# Putri_Shaqila_GT1.net
KiCad netlist of a schematic drawn in EAGLE
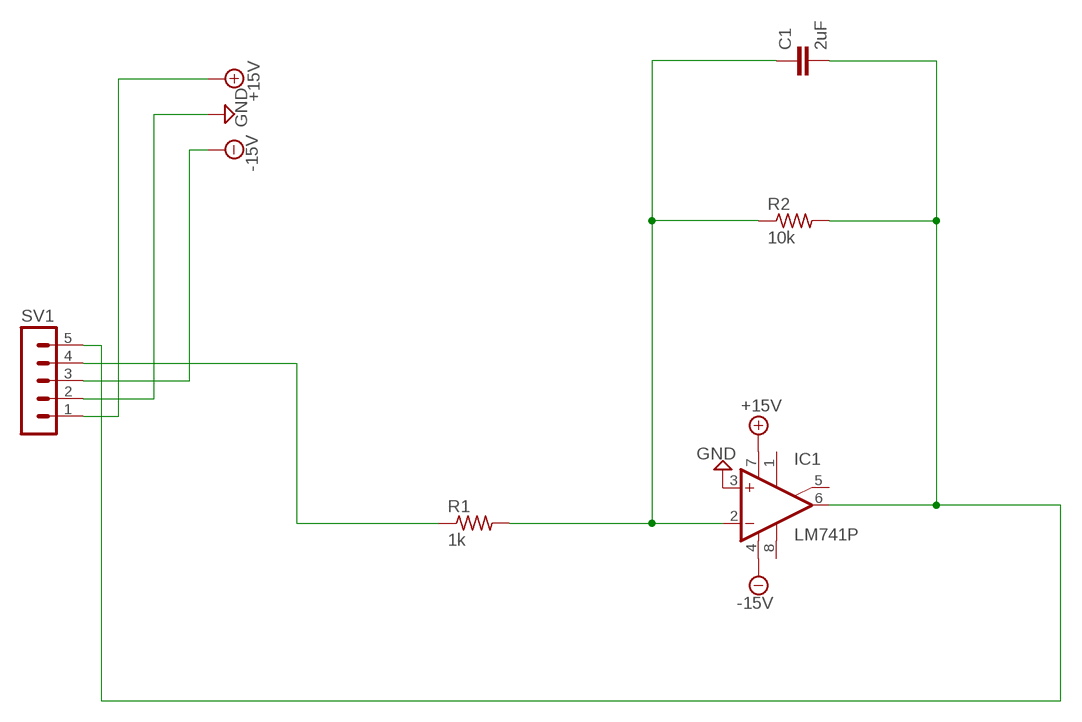
[diagram p0: schematic, sheet 1]

(export (version "E")
  (design (tool "Eeschema 10.0.6"))
  (components
    (comp (ref "C1")
      (value "2uF")
      (footprint "eagle-import:C0603")
      (libsource (lib "eagle-import") (part "C-EUC0603"))
    )
    (comp (ref "IC1")
      (value "LM741P")
      (footprint "eagle-import:DIL08")
      (libsource (lib "eagle-import") (part "741PLM"))
    )
    (comp (ref "R1")
      (value "1k")
      (footprint "eagle-import:R0603")
      (libsource (lib "eagle-import") (part "R-US_R0603"))
    )
    (comp (ref "R2")
      (value "10k")
      (footprint "eagle-import:R0603")
      (libsource (lib "eagle-import") (part "R-US_R0603"))
    )
    (comp (ref "SV1")
      (value "MA05-1")
      (footprint "eagle-import:MA05-1")
      (libsource (lib "eagle-import") (part "MA05-1"))
    )
  )
  (nets
    (net (code "1") (name "+15V") (class "Default")
      (node (ref "IC1") (pin "7") (pinfunction "V+_7") (pintype "power_in"))
      (node (ref "SV1") (pin "1") (pinfunction "1_1") (pintype "passive"))
    )
    (net (code "2") (name "-15V") (class "Default")
      (node (ref "IC1") (pin "4") (pinfunction "V-_4") (pintype "power_in"))
      (node (ref "SV1") (pin "3") (pinfunction "3_3") (pintype "passive"))
    )
    (net (code "3") (name "GND") (class "Default")
      (node (ref "IC1") (pin "3") (pinfunction "+IN_3") (pintype "input"))
      (node (ref "SV1") (pin "2") (pinfunction "2_2") (pintype "passive"))
    )
    (net (code "4") (name "Net-(IC1--IN)") (class "Default")
      (node (ref "C1") (pin "1") (pinfunction "1_1") (pintype "passive"))
      (node (ref "IC1") (pin "2") (pinfunction "-IN_2") (pintype "input"))
      (node (ref "R1") (pin "2") (pinfunction "2_2") (pintype "passive"))
      (node (ref "R2") (pin "1") (pinfunction "1_1") (pintype "passive"))
    )
    (net (code "5") (name "Net-(IC1-OUT)") (class "Default")
      (node (ref "C1") (pin "2") (pinfunction "2_2") (pintype "passive"))
      (node (ref "IC1") (pin "6") (pinfunction "OUT_6") (pintype "output"))
      (node (ref "R2") (pin "2") (pinfunction "2_2") (pintype "passive"))
    )
    (net (code "6") (name "Net-(R1-Pad1)") (class "Default")
      (node (ref "R1") (pin "1") (pinfunction "1_1") (pintype "passive"))
      (node (ref "SV1") (pin "4") (pinfunction "4_4") (pintype "passive"))
    )
    (net (code "7") (name "unconnected-(IC1-ON1-Pad1)") (class "Default")
      (node (ref "IC1") (pin "1") (pinfunction "ON1_1") (pintype "passive"))
    )
    (net (code "8") (name "unconnected-(IC1-ON2-Pad5)") (class "Default")
      (node (ref "IC1") (pin "5") (pinfunction "ON2_5") (pintype "passive"))
    )
    (net (code "9") (name "unconnected-(IC1-OPT-Pad8)") (class "Default")
      (node (ref "IC1") (pin "8") (pinfunction "OPT_8") (pintype "passive"))
    )
    (net (code "10") (name "unconnected-(SV1-Pad5)") (class "Default")
      (node (ref "SV1") (pin "5") (pinfunction "5_5") (pintype "passive"))
    )
  )
)
